# Shematic.net
KiCad netlist of a schematic drawn in Altium Designer
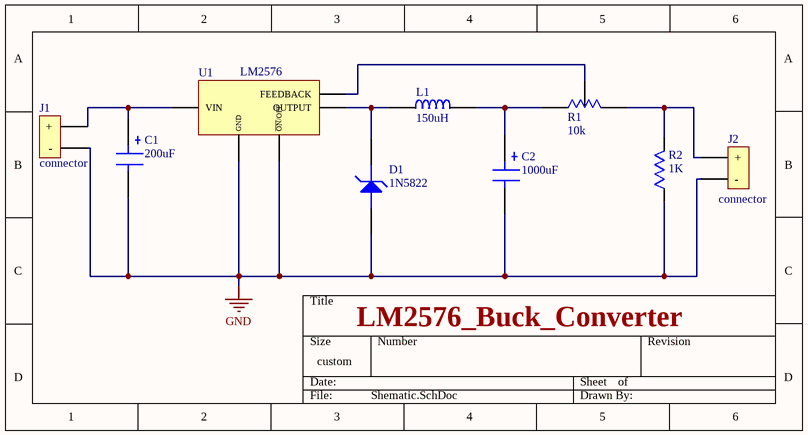
[diagram p0: Shematic.SchDoc]

(export (version "E")
  (design (tool "Eeschema 10.0.6"))
  (components
    (comp (ref "C1")
      (value "200uF")
      (footprint "C_elec - duplicate")
      (libsource (lib "LM2576_Buck_Converter_Sch_library") (part "cap_elec"))
    )
    (comp (ref "C2")
      (value "1000uF")
      (footprint "C_elec - duplicate")
      (libsource (lib "LM2576_Buck_Converter_Sch_library") (part "cap_elec"))
    )
    (comp (ref "D1")
      (value "1N5822")
      (footprint "1N5822 - duplicate1")
      (libsource (lib "LM2576_Buck_Converter_Sch_library") (part "1N5822"))
    )
    (comp (ref "J1")
      (value "connector")
      (footprint "2PIN_Connector")
      (libsource (lib "") (part "2PIN_Connector_1"))
    )
    (comp (ref "J2")
      (value "connector")
      (footprint "2PIN_Connector")
      (libsource (lib "LM2576_Buck_Converter_Sch_library") (part "2PIN_Connector"))
    )
    (comp (ref "L1")
      (value "150uH")
      (footprint "150uH Indicator - duplicate")
      (libsource (lib "LM2576_Buck_Converter_Sch_library") (part "150uH"))
    )
    (comp (ref "R1")
      (value "10k")
      (footprint "variabel resistor - duplicate")
      (libsource (lib "LM2576_Buck_Converter_Sch_library") (part "variable Resistor"))
    )
    (comp (ref "R2")
      (value "1K")
      (footprint "R(0805)")
      (libsource (lib "LM2576_Buck_Converter_Sch_library") (part "Res"))
    )
    (comp (ref "U1")
      (value "LM2576")
      (footprint "LM2576 - duplicate")
      (libsource (lib "LM2576_Buck_Converter_Sch_library") (part "LM2576"))
    )
  )
  (nets
    (net (code "1") (name "GND") (class "Default")
      (node (ref "C1") (pin "2") (pinfunction "2_2") (pintype "passive"))
      (node (ref "C2") (pin "2") (pinfunction "2_2") (pintype "passive"))
      (node (ref "D1") (pin "1") (pinfunction "Anode_1") (pintype "passive"))
      (node (ref "J1") (pin "2") (pinfunction "-_2") (pintype "passive"))
      (node (ref "J2") (pin "2") (pinfunction "-_2") (pintype "passive"))
      (node (ref "R2") (pin "1") (pinfunction "1_1") (pintype "passive"))
      (node (ref "U1") (pin "3") (pinfunction "GND_3") (pintype "passive"))
      (node (ref "U1") (pin "5") (pinfunction "~{ON}/OFF_5") (pintype "passive"))
    )
    (net (code "2") (name "Net-(C2-Pad1)") (class "Default")
      (node (ref "C2") (pin "1") (pinfunction "1_1") (pintype "passive"))
      (node (ref "L1") (pin "2") (pinfunction "2_2") (pintype "passive"))
      (node (ref "R1") (pin "1") (pinfunction "1_1") (pintype "passive"))
    )
    (net (code "3") (name "Net-(D1-Cathode)") (class "Default")
      (node (ref "D1") (pin "2") (pinfunction "Cathode_2") (pintype "passive"))
      (node (ref "L1") (pin "1") (pinfunction "1_1") (pintype "passive"))
      (node (ref "U1") (pin "2") (pinfunction "OUTPUT_2") (pintype "passive"))
    )
    (net (code "4") (name "Net-(J1-+)") (class "Default")
      (node (ref "C1") (pin "1") (pinfunction "1_1") (pintype "passive"))
      (node (ref "J1") (pin "1") (pinfunction "+_1") (pintype "passive"))
      (node (ref "U1") (pin "1") (pinfunction "VIN_1") (pintype "passive"))
    )
    (net (code "5") (name "Net-(J2-+)") (class "Default")
      (node (ref "J2") (pin "1") (pinfunction "+_1") (pintype "passive"))
      (node (ref "R1") (pin "3") (pinfunction "3_3") (pintype "passive"))
      (node (ref "R2") (pin "2") (pinfunction "2_2") (pintype "passive"))
    )
    (net (code "6") (name "Net-(U1-FEEDBACK)") (class "Default")
      (node (ref "R1") (pin "2") (pinfunction "2_2") (pintype "passive"))
      (node (ref "U1") (pin "4") (pinfunction "FEEDBACK_4") (pintype "passive"))
    )
  )
)
